# Gastroscopy-Controller_MCU.net
KiCad netlist of a schematic drawn in Altium Designer
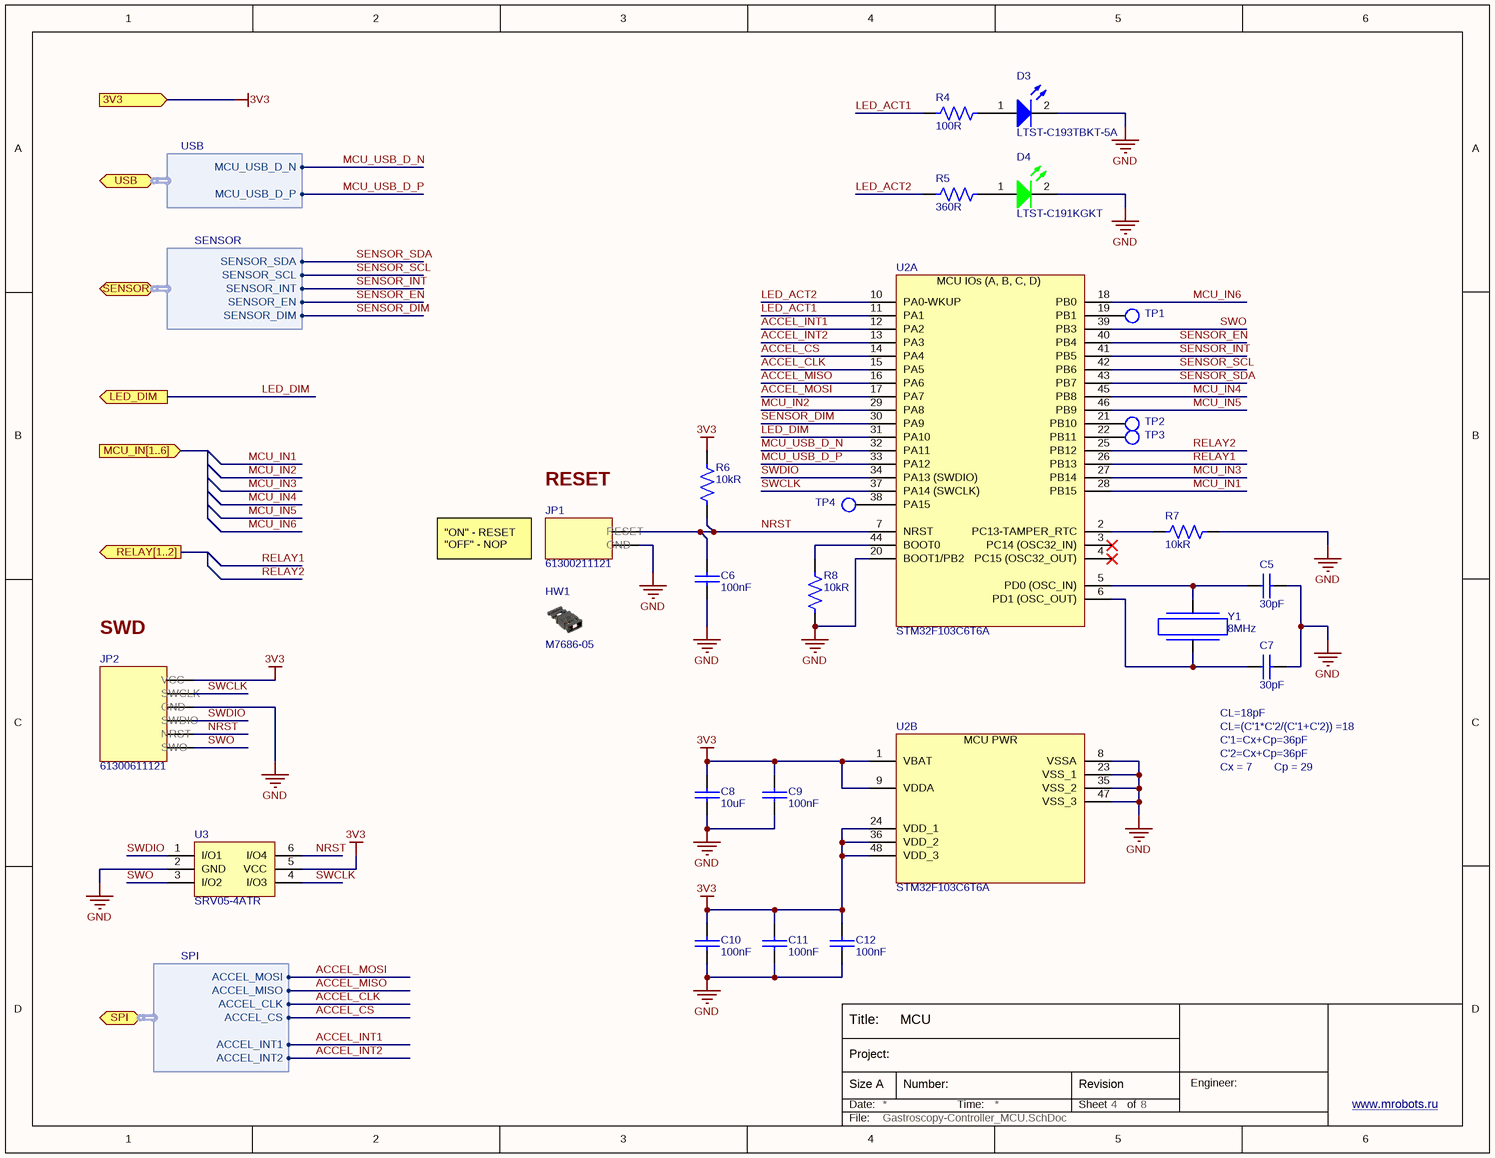
[diagram p0: Gastroscopy-Controller_MCU.SchDoc]

(export (version "E")
  (design (tool "Eeschema 10.0.6"))
  (components
    (comp (ref "C5")
      (value "30pF")
      (footprint "CAP_0603")
      (description "CAP CER 30PF 50V NPO 0603")
      (fields
        (field (name "MANUFACTURER") "Yageo")
        (field (name "MANUFACTURER PART NUMBER") "CC0603JRNPO9BN300")
      )
      (libsource (lib "Gastroscopy-Controller") (part "CC0603JRNPO9BN300"))
    )
    (comp (ref "C6")
      (value "100nF")
      (footprint "CAP_0603")
      (description "CAP CER 0.1UF 50V X7R 0603")
      (fields (field (name "TOLERANCE") "10%"))
      (libsource (lib "Gastroscopy-Controller") (part "CL10B104KB8NNNL"))
    )
    (comp (ref "C7")
      (value "30pF")
      (footprint "CAP_0603")
      (description "CAP CER 30PF 50V NPO 0603")
      (fields
        (field (name "MANUFACTURER") "Yageo")
        (field (name "MANUFACTURER PART NUMBER") "CC0603JRNPO9BN300")
      )
      (libsource (lib "Gastroscopy-Controller") (part "CC0603JRNPO9BN300"))
    )
    (comp (ref "C8")
      (value "10uF")
      (footprint "CAP_0805")
      (description "CAP CER 10UF 16V X7R 0805")
      (fields (field (name "TOLERANCE") "10%") (field (name "VOLTAGE") "16V"))
      (libsource (lib "Gastroscopy-Controller") (part "CL21B106KOQNNNE"))
    )
    (comp (ref "C9")
      (value "100nF")
      (footprint "CAP_0603")
      (description "CAP CER 0.1UF 50V X7R 0603")
      (fields (field (name "TOLERANCE") "10%"))
      (libsource (lib "Gastroscopy-Controller") (part "CL10B104KB8NNNL"))
    )
    (comp (ref "C10")
      (value "100nF")
      (footprint "CAP_0603")
      (description "CAP CER 0.1UF 50V X7R 0603")
      (fields (field (name "TOLERANCE") "10%"))
      (libsource (lib "Gastroscopy-Controller") (part "CL10B104KB8NNNL"))
    )
    (comp (ref "C11")
      (value "100nF")
      (footprint "CAP_0603")
      (description "CAP CER 0.1UF 50V X7R 0603")
      (fields (field (name "TOLERANCE") "10%"))
      (libsource (lib "Gastroscopy-Controller") (part "CL10B104KB8NNNL"))
    )
    (comp (ref "C12")
      (value "100nF")
      (footprint "CAP_0603")
      (description "CAP CER 0.1UF 50V X7R 0603")
      (fields (field (name "TOLERANCE") "10%"))
      (libsource (lib "Gastroscopy-Controller") (part "CL10B104KB8NNNL"))
    )
    (comp (ref "D3")
      (value "LTST-C193TBKT-5A")
      (footprint "L_0603_BLUE")
      (description "LED BLUE CLEAR CHIP SMD")
      (libsource (lib "Gastroscopy-Controller") (part "LTST-C193TBKT-5A"))
    )
    (comp (ref "D4")
      (value "LTST-C191KGKT")
      (footprint "L_0603_GREEN")
      (description "LED GREEN CLEAR SMD")
      (libsource (lib "Gastroscopy-Controller") (part "LTST-C191KGKT"))
    )
    (comp (ref "HW1")
      (value "M7686-05")
      (description "CLOSED TOP JUMPER SOCKET")
      (libsource (lib "Gastroscopy-Controller") (part "M7686-05"))
    )
    (comp (ref "JP1")
      (value "61300211121")
      (footprint "PLS-2")
      (description "CONN HEADER VERT 2POS 2.54MM")
      (libsource (lib "Gastroscopy-Controller") (part "61300211121"))
    )
    (comp (ref "JP2")
      (value "61300611121")
      (footprint "PLS-6")
      (description "CONN HEADER VERT 6POS 2.54MM")
      (libsource (lib "Gastroscopy-Controller") (part "61300611121"))
    )
    (comp (ref "R4")
      (value "100R")
      (footprint "RES_0603")
      (description "RES 100 OHM 1% 1/10W 0603")
      (fields (field (name "TOLERANCE") "1%"))
      (libsource (lib "Gastroscopy-Controller") (part "RC0603FR-07100RL"))
    )
    (comp (ref "R5")
      (value "360R")
      (footprint "RES_0603")
      (description "RES 360 OHM 1% 1/10W 0603")
      (fields (field (name "TOLERANCE") "1%"))
      (libsource (lib "Gastroscopy-Controller") (part "RC0603FR-07360RL"))
    )
    (comp (ref "R6")
      (value "10kR")
      (footprint "RES_0603")
      (description "RES 10K OHM 1% 1/10W 0603")
      (fields (field (name "TOLERANCE") "1%"))
      (libsource (lib "Gastroscopy-Controller") (part "RC0603FR-0710KL"))
    )
    (comp (ref "R7")
      (value "10kR")
      (footprint "RES_0603")
      (description "RES 10K OHM 1% 1/10W 0603")
      (fields (field (name "TOLERANCE") "1%"))
      (libsource (lib "Gastroscopy-Controller") (part "RC0603FR-0710KL"))
    )
    (comp (ref "R8")
      (value "10kR")
      (footprint "RES_0603")
      (description "RES 10K OHM 1% 1/10W 0603")
      (fields (field (name "TOLERANCE") "1%"))
      (libsource (lib "Gastroscopy-Controller") (part "RC0603FR-0710KL"))
    )
    (comp (ref "TP1")
      (value "TEST_POINT_SMT")
      (footprint "TEST_POINT_SMT")
      (description "STM TEST POINT")
      (libsource (lib "Industrial-Controller") (part "TEST_POINT_SMT"))
    )
    (comp (ref "TP2")
      (value "TEST_POINT_SMT")
      (footprint "TEST_POINT_SMT")
      (description "STM TEST POINT")
      (libsource (lib "Industrial-Controller") (part "TEST_POINT_SMT"))
    )
    (comp (ref "TP3")
      (value "TEST_POINT_SMT")
      (footprint "TEST_POINT_SMT")
      (description "STM TEST POINT")
      (libsource (lib "Industrial-Controller") (part "TEST_POINT_SMT"))
    )
    (comp (ref "TP4")
      (value "TEST_POINT_SMT")
      (footprint "TEST_POINT_SMT")
      (description "STM TEST POINT")
      (libsource (lib "Industrial-Controller") (part "TEST_POINT_SMT"))
    )
    (comp (ref "U2")
      (value "STM32F103C6T6A")
      (footprint "LQFP48")
      (description "IC MCU 32BIT 32KB FLASH 48LQFP")
      (libsource (lib "Industrial-Controller") (part "STM32F103C6T6A"))
    )
    (comp (ref "U3")
      (value "SRV05-4ATR")
      (footprint "SOT-23-6")
      (description "TVS DIODE 5VWM 17.5VC SOT23-6")
      (libsource (lib "Gastroscopy-Controller") (part "SRV05-4ATR"))
    )
    (comp (ref "Y1")
      (value "8MHz")
      (footprint "HC-49/US")
      (description "CRYSTAL 8.0000MHZ 18PF TH")
      (fields (field (name "TOLERANCE") "30ppm"))
      (libsource (lib "Gastroscopy-Controller") (part "ATS080B-E"))
    )
  )
  (nets
    (net (code "4") (name "/ACCEL_CLK") (class "Default")
      (node (ref "U2") (pin "15") (pinfunction "PA5_15") (pintype "passive"))
    )
    (net (code "5") (name "/ACCEL_CS") (class "Default")
      (node (ref "U2") (pin "14") (pinfunction "PA4_14") (pintype "passive"))
    )
    (net (code "6") (name "/ACCEL_INT1") (class "Default")
      (node (ref "U2") (pin "12") (pinfunction "PA2_12") (pintype "passive"))
    )
    (net (code "7") (name "/ACCEL_INT2") (class "Default")
      (node (ref "U2") (pin "13") (pinfunction "PA3_13") (pintype "passive"))
    )
    (net (code "8") (name "/ACCEL_MISO") (class "Default")
      (node (ref "U2") (pin "16") (pinfunction "PA6_16") (pintype "passive"))
    )
    (net (code "9") (name "/ACCEL_MOSI") (class "Default")
      (node (ref "U2") (pin "17") (pinfunction "PA7_17") (pintype "passive"))
    )
    (net (code "10") (name "/LED_ACT1") (class "Default")
      (node (ref "R4") (pin "1") (pinfunction "1_1") (pintype "passive"))
      (node (ref "U2") (pin "11") (pinfunction "PA1_11") (pintype "passive"))
    )
    (net (code "11") (name "/LED_ACT2") (class "Default")
      (node (ref "R5") (pin "1") (pinfunction "1_1") (pintype "passive"))
      (node (ref "U2") (pin "10") (pinfunction "PA0-WKUP_10") (pintype "passive"))
    )
    (net (code "12") (name "/LED_DIM") (class "Default")
      (node (ref "U2") (pin "31") (pinfunction "PA10_31") (pintype "passive"))
    )
    (net (code "13") (name "/MCU_IN1") (class "Default")
      (node (ref "U2") (pin "28") (pinfunction "PB15_28") (pintype "passive"))
    )
    (net (code "14") (name "/MCU_IN2") (class "Default")
      (node (ref "U2") (pin "29") (pinfunction "PA8_29") (pintype "passive"))
    )
    (net (code "15") (name "/MCU_IN3") (class "Default")
      (node (ref "U2") (pin "27") (pinfunction "PB14_27") (pintype "passive"))
    )
    (net (code "16") (name "/MCU_IN4") (class "Default")
      (node (ref "U2") (pin "45") (pinfunction "PB8_45") (pintype "passive"))
    )
    (net (code "17") (name "/MCU_IN5") (class "Default")
      (node (ref "U2") (pin "46") (pinfunction "PB9_46") (pintype "passive"))
    )
    (net (code "18") (name "/MCU_IN6") (class "Default")
      (node (ref "U2") (pin "18") (pinfunction "PB0_18") (pintype "passive"))
    )
    (net (code "20") (name "/MCU_USB_D_N") (class "Default")
      (node (ref "U2") (pin "32") (pinfunction "PA11_32") (pintype "passive"))
    )
    (net (code "21") (name "/MCU_USB_D_P") (class "Default")
      (node (ref "U2") (pin "33") (pinfunction "PA12_33") (pintype "passive"))
    )
    (net (code "22") (name "/NRST") (class "Default")
      (node (ref "C6") (pin "1") (pinfunction "1_1") (pintype "passive"))
      (node (ref "JP1") (pin "1") (pinfunction "1_1") (pintype "passive"))
      (node (ref "JP2") (pin "5") (pinfunction "5_5") (pintype "passive"))
      (node (ref "R6") (pin "2") (pinfunction "2_2") (pintype "passive"))
      (node (ref "U2") (pin "7") (pinfunction "NRST_7") (pintype "passive"))
      (node (ref "U3") (pin "6") (pinfunction "I/O4_6") (pintype "passive"))
    )
    (net (code "23") (name "/RELAY1") (class "Default")
      (node (ref "U2") (pin "26") (pinfunction "PB13_26") (pintype "passive"))
    )
    (net (code "24") (name "/RELAY2") (class "Default")
      (node (ref "U2") (pin "25") (pinfunction "PB12_25") (pintype "passive"))
    )
    (net (code "26") (name "/SENSOR_DIM") (class "Default")
      (node (ref "U2") (pin "30") (pinfunction "PA9_30") (pintype "passive"))
    )
    (net (code "27") (name "/SENSOR_EN") (class "Default")
      (node (ref "U2") (pin "40") (pinfunction "PB4_40") (pintype "passive"))
    )
    (net (code "28") (name "/SENSOR_INT") (class "Default")
      (node (ref "U2") (pin "41") (pinfunction "PB5_41") (pintype "passive"))
    )
    (net (code "29") (name "/SENSOR_SCL") (class "Default")
      (node (ref "U2") (pin "42") (pinfunction "PB6_42") (pintype "passive"))
    )
    (net (code "30") (name "/SENSOR_SDA") (class "Default")
      (node (ref "U2") (pin "43") (pinfunction "PB7_43") (pintype "passive"))
    )
    (net (code "31") (name "/SWCLK") (class "Default")
      (node (ref "JP2") (pin "2") (pinfunction "2_2") (pintype "passive"))
      (node (ref "U2") (pin "37") (pinfunction "PA14_(SWCLK)_37") (pintype "passive"))
      (node (ref "U3") (pin "4") (pinfunction "I/O3_4") (pintype "passive"))
    )
    (net (code "32") (name "/SWDIO") (class "Default")
      (node (ref "JP2") (pin "4") (pinfunction "4_4") (pintype "passive"))
      (node (ref "U2") (pin "34") (pinfunction "PA13_(SWDIO)_34") (pintype "passive"))
      (node (ref "U3") (pin "1") (pinfunction "I/O1_1") (pintype "passive"))
    )
    (net (code "33") (name "/SWO") (class "Default")
      (node (ref "JP2") (pin "6") (pinfunction "6_6") (pintype "passive"))
      (node (ref "U2") (pin "39") (pinfunction "PB3_39") (pintype "passive"))
      (node (ref "U3") (pin "3") (pinfunction "I/O2_3") (pintype "passive"))
    )
    (net (code "37") (name "3V3") (class "Default")
      (node (ref "C10") (pin "1") (pinfunction "1_1") (pintype "passive"))
      (node (ref "C11") (pin "1") (pinfunction "1_1") (pintype "passive"))
      (node (ref "C12") (pin "1") (pinfunction "1_1") (pintype "passive"))
      (node (ref "C8") (pin "2") (pinfunction "2_2") (pintype "passive"))
      (node (ref "C9") (pin "1") (pinfunction "1_1") (pintype "passive"))
      (node (ref "JP2") (pin "1") (pinfunction "1_1") (pintype "passive"))
      (node (ref "R6") (pin "1") (pinfunction "1_1") (pintype "passive"))
      (node (ref "U2") (pin "1") (pinfunction "VBAT_1") (pintype "passive"))
      (node (ref "U2") (pin "24") (pinfunction "VDD_1_24") (pintype "passive"))
      (node (ref "U2") (pin "36") (pinfunction "VDD_2_36") (pintype "passive"))
      (node (ref "U2") (pin "48") (pinfunction "VDD_3_48") (pintype "passive"))
      (node (ref "U2") (pin "9") (pinfunction "VDDA_9") (pintype "passive"))
      (node (ref "U3") (pin "5") (pinfunction "VCC_5") (pintype "passive"))
    )
    (net (code "38") (name "GND") (class "Default")
      (node (ref "C10") (pin "2") (pinfunction "2_2") (pintype "passive"))
      (node (ref "C11") (pin "2") (pinfunction "2_2") (pintype "passive"))
      (node (ref "C12") (pin "2") (pinfunction "2_2") (pintype "passive"))
      (node (ref "C5") (pin "2") (pinfunction "2_2") (pintype "passive"))
      (node (ref "C6") (pin "2") (pinfunction "2_2") (pintype "passive"))
      (node (ref "C7") (pin "2") (pinfunction "2_2") (pintype "passive"))
      (node (ref "C8") (pin "1") (pinfunction "1_1") (pintype "passive"))
      (node (ref "C9") (pin "2") (pinfunction "2_2") (pintype "passive"))
      (node (ref "D3") (pin "2") (pinfunction "K_2") (pintype "passive"))
      (node (ref "D4") (pin "2") (pinfunction "K_2") (pintype "passive"))
      (node (ref "JP1") (pin "2") (pinfunction "2_2") (pintype "passive"))
      (node (ref "JP2") (pin "3") (pinfunction "3_3") (pintype "passive"))
      (node (ref "R7") (pin "1") (pinfunction "1_1") (pintype "passive"))
      (node (ref "R8") (pin "1") (pinfunction "1_1") (pintype "passive"))
      (node (ref "U2") (pin "20") (pinfunction "BOOT1/PB2_20") (pintype "passive"))
      (node (ref "U2") (pin "23") (pinfunction "VSS_1_23") (pintype "passive"))
      (node (ref "U2") (pin "35") (pinfunction "VSS_2_35") (pintype "passive"))
      (node (ref "U2") (pin "47") (pinfunction "VSS_3_47") (pintype "passive"))
      (node (ref "U2") (pin "8") (pinfunction "VSSA_8") (pintype "passive"))
      (node (ref "U3") (pin "2") (pinfunction "GND_2") (pintype "passive"))
    )
    (net (code "39") (name "Net-(D3-A)") (class "Default")
      (node (ref "D3") (pin "1") (pinfunction "A_1") (pintype "passive"))
      (node (ref "R4") (pin "2") (pinfunction "2_2") (pintype "passive"))
    )
    (net (code "40") (name "Net-(D4-A)") (class "Default")
      (node (ref "D4") (pin "1") (pinfunction "A_1") (pintype "passive"))
      (node (ref "R5") (pin "2") (pinfunction "2_2") (pintype "passive"))
    )
    (net (code "41") (name "Net-(U2A-BOOT0)") (class "Default")
      (node (ref "R8") (pin "2") (pinfunction "2_2") (pintype "passive"))
      (node (ref "U2") (pin "44") (pinfunction "BOOT0_44") (pintype "passive"))
    )
    (net (code "42") (name "Net-(U2A-PA15)") (class "Default")
      (node (ref "TP4") (pin "1") (pinfunction "1_1") (pintype "passive"))
      (node (ref "U2") (pin "38") (pinfunction "PA15_38") (pintype "passive"))
    )
    (net (code "43") (name "Net-(U2A-PB1)") (class "Default")
      (node (ref "TP1") (pin "1") (pinfunction "1_1") (pintype "passive"))
      (node (ref "U2") (pin "19") (pinfunction "PB1_19") (pintype "passive"))
    )
    (net (code "44") (name "Net-(U2A-PB10)") (class "Default")
      (node (ref "TP2") (pin "1") (pinfunction "1_1") (pintype "passive"))
      (node (ref "U2") (pin "21") (pinfunction "PB10_21") (pintype "passive"))
    )
    (net (code "45") (name "Net-(U2A-PB11)") (class "Default")
      (node (ref "TP3") (pin "1") (pinfunction "1_1") (pintype "passive"))
      (node (ref "U2") (pin "22") (pinfunction "PB11_22") (pintype "passive"))
    )
    (net (code "46") (name "Net-(U2A-PC13-TAMPER_RTC)") (class "Default")
      (node (ref "R7") (pin "2") (pinfunction "2_2") (pintype "passive"))
      (node (ref "U2") (pin "2") (pinfunction "PC13-TAMPER_RTC_2") (pintype "passive"))
    )
    (net (code "47") (name "Net-(U2A-PD0_(OSC_IN))") (class "Default")
      (node (ref "C5") (pin "1") (pinfunction "1_1") (pintype "passive"))
      (node (ref "U2") (pin "5") (pinfunction "PD0_(OSC_IN)_5") (pintype "passive"))
      (node (ref "Y1") (pin "2") (pinfunction "2_2") (pintype "passive"))
    )
    (net (code "48") (name "Net-(U2A-PD1_(OSC_OUT))") (class "Default")
      (node (ref "C7") (pin "1") (pinfunction "1_1") (pintype "passive"))
      (node (ref "U2") (pin "6") (pinfunction "PD1_(OSC_OUT)_6") (pintype "passive"))
      (node (ref "Y1") (pin "1") (pinfunction "1_1") (pintype "passive"))
    )
    (net (code "49") (name "unconnected-(U2A-PC14_(OSC32_IN)-Pad3)") (class "Default")
      (node (ref "U2") (pin "3") (pinfunction "PC14_(OSC32_IN)_3") (pintype "passive+no_connect"))
    )
    (net (code "50") (name "unconnected-(U2A-PC15_(OSC32_OUT)-Pad4)") (class "Default")
      (node (ref "U2") (pin "4") (pinfunction "PC15_(OSC32_OUT)_4") (pintype "passive+no_connect"))
    )
  )
)
